# altium_kicad.net
KiCad netlist of a schematic drawn in Altium Designer
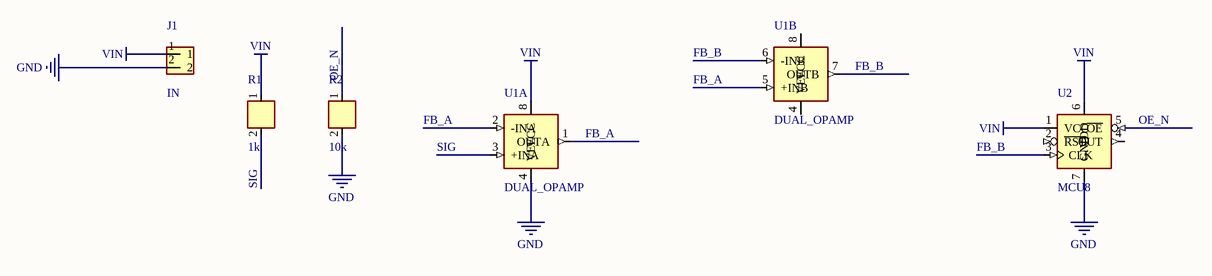
[diagram p0: altium_kicad.SchDoc]

(export (version "E")
  (design (tool "Eeschema 10.0.6"))
  (components
    (comp (ref "J1")
      (value "IN")
      (footprint "altium_kicad:PinHeader_1x02")
      (libsource (lib "altium_kicad") (part "CONN2"))
    )
    (comp (ref "R1")
      (value "1k")
      (footprint "altium_kicad:R0603")
      (libsource (lib "altium_kicad") (part "R_V"))
    )
    (comp (ref "R2")
      (value "10k")
      (footprint "altium_kicad:R0603")
      (libsource (lib "altium_kicad") (part "R_V"))
    )
    (comp (ref "U1")
      (value "DUAL_OPAMP")
      (footprint "altium_kicad:SOIC8")
      (libsource (lib "altium_kicad") (part "DUAL_OPAMP"))
    )
    (comp (ref "U2")
      (value "MCU8")
      (footprint "altium_kicad:SOIC8")
      (libsource (lib "altium_kicad") (part "MCU8"))
    )
  )
  (nets
    (net (code "1") (name "/FB_A") (class "Default")
      (node (ref "U1") (pin "1") (pinfunction "OUTA_1") (pintype "output"))
      (node (ref "U1") (pin "2") (pinfunction "-INA_2") (pintype "input"))
      (node (ref "U1") (pin "5") (pinfunction "+INB_5") (pintype "input"))
    )
    (net (code "2") (name "/FB_B") (class "Default")
      (node (ref "U1") (pin "6") (pinfunction "-INB_6") (pintype "input"))
      (node (ref "U1") (pin "7") (pinfunction "OUTB_7") (pintype "output"))
      (node (ref "U2") (pin "3") (pinfunction "CLK_3") (pintype "input"))
    )
    (net (code "3") (name "/OE_N") (class "Default")
      (node (ref "R2") (pin "1") (pinfunction "~_1") (pintype "passive"))
      (node (ref "U2") (pin "5") (pinfunction "~{OE}_5") (pintype "input"))
    )
    (net (code "4") (name "/SIG") (class "Default")
      (node (ref "R1") (pin "2") (pinfunction "~_2") (pintype "passive"))
      (node (ref "U1") (pin "3") (pinfunction "+INA_3") (pintype "input"))
    )
    (net (code "5") (name "GND") (class "Default")
      (node (ref "J1") (pin "2") (pinfunction "2_2") (pintype "passive"))
      (node (ref "R2") (pin "2") (pinfunction "~_2") (pintype "passive"))
      (node (ref "U1") (pin "4") (pinfunction "VEE_4") (pintype "power_in"))
      (node (ref "U2") (pin "7") (pinfunction "GND_7") (pintype "power_in"))
    )
    (net (code "6") (name "VIN") (class "Default")
      (node (ref "J1") (pin "1") (pinfunction "1_1") (pintype "passive"))
      (node (ref "R1") (pin "1") (pinfunction "~_1") (pintype "passive"))
      (node (ref "U1") (pin "8") (pinfunction "VCC_8") (pintype "power_in"))
      (node (ref "U2") (pin "1") (pinfunction "VCC_1") (pintype "power_in"))
      (node (ref "U2") (pin "6") (pinfunction "VDD_6") (pintype "power_in"))
    )
    (net (code "7") (name "unconnected-(U1B-VCC-Pad8)") (class "Default")
      (node (ref "U1") (pin "8") (pinfunction "VCC_8") (pintype "power_in"))
    )
    (net (code "8") (name "unconnected-(U1B-VEE-Pad4)") (class "Default")
      (node (ref "U1") (pin "4") (pinfunction "VEE_4") (pintype "power_in"))
    )
    (net (code "9") (name "unconnected-(U2-OUT-Pad4)") (class "Default")
      (node (ref "U2") (pin "4") (pinfunction "OUT_4") (pintype "output"))
    )
    (net (code "10") (name "unconnected-(U2-TP-Pad8)") (class "Default")
      (node (ref "U2") (pin "8") (pinfunction "TP_8") (pintype "passive"))
    )
    (net (code "11") (name "unconnected-(U2-~{RST}-Pad2)") (class "Default")
      (node (ref "U2") (pin "2") (pinfunction "~{RST}_2") (pintype "input"))
    )
  )
)
